# pic3.net
KiCad netlist of a schematic drawn in EAGLE
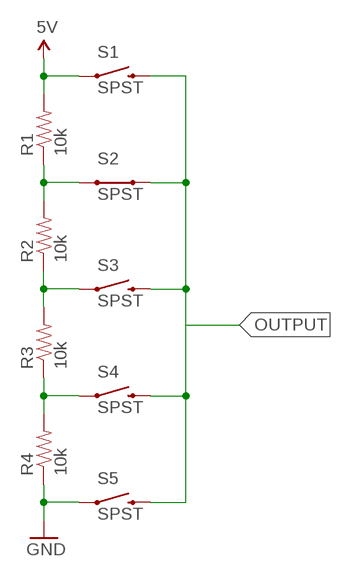
[diagram p0: schematic, sheet 1]

(export (version "E")
  (design (tool "Eeschema 10.0.6"))
  (components
    (comp (ref "R1")
      (value "10k")
      (footprint "eagle-import:0603-RES")
      (fields (field (name "PROD_ID") "RES-00818"))
      (libsource (lib "eagle-import") (part "330OHM1/10W1%(0603)"))
    )
    (comp (ref "R2")
      (value "10k")
      (footprint "eagle-import:0603-RES")
      (fields (field (name "PROD_ID") "RES-00818"))
      (libsource (lib "eagle-import") (part "330OHM1/10W1%(0603)"))
    )
    (comp (ref "R3")
      (value "10k")
      (footprint "eagle-import:0603-RES")
      (fields (field (name "PROD_ID") "RES-00818"))
      (libsource (lib "eagle-import") (part "330OHM1/10W1%(0603)"))
    )
    (comp (ref "R4")
      (value "10k")
      (footprint "eagle-import:0603-RES")
      (fields (field (name "PROD_ID") "RES-00818"))
      (libsource (lib "eagle-import") (part "330OHM1/10W1%(0603)"))
    )
    (comp (ref "S1")
      (value "SPST")
      (footprint "eagle-import:TACTILE-PTH-12MM")
      (libsource (lib "eagle-import") (part "SWITCH-MOMENTARY-212MM"))
    )
    (comp (ref "S2")
      (value "SPST")
      (footprint "eagle-import:TACTILE-PTH-12MM")
      (libsource (lib "eagle-import") (part "SWITCH-MOMENTARY-2-CLOSED"))
    )
    (comp (ref "S3")
      (value "SPST")
      (footprint "eagle-import:TACTILE-PTH-12MM")
      (libsource (lib "eagle-import") (part "SWITCH-MOMENTARY-212MM"))
    )
    (comp (ref "S4")
      (value "SPST")
      (footprint "eagle-import:TACTILE-PTH-12MM")
      (libsource (lib "eagle-import") (part "SWITCH-MOMENTARY-212MM"))
    )
    (comp (ref "S5")
      (value "SPST")
      (footprint "eagle-import:TACTILE-PTH-12MM")
      (libsource (lib "eagle-import") (part "SWITCH-MOMENTARY-212MM"))
    )
  )
  (nets
    (net (code "1") (name "5V") (class "Default")
      (node (ref "R1") (pin "2") (pinfunction "2_2") (pintype "passive"))
      (node (ref "S1") (pin "1") (pinfunction "1_1") (pintype "passive"))
    )
    (net (code "2") (name "GND") (class "Default")
      (node (ref "R4") (pin "1") (pinfunction "1_1") (pintype "passive"))
      (node (ref "S5") (pin "1") (pinfunction "1_1") (pintype "passive"))
    )
    (net (code "3") (name "Net-(R1-Pad1)") (class "Default")
      (node (ref "R1") (pin "1") (pinfunction "1_1") (pintype "passive"))
      (node (ref "R2") (pin "2") (pinfunction "2_2") (pintype "passive"))
      (node (ref "S2") (pin "1") (pinfunction "1_1") (pintype "passive"))
    )
    (net (code "4") (name "Net-(R2-Pad1)") (class "Default")
      (node (ref "R2") (pin "1") (pinfunction "1_1") (pintype "passive"))
      (node (ref "R3") (pin "2") (pinfunction "2_2") (pintype "passive"))
      (node (ref "S3") (pin "1") (pinfunction "1_1") (pintype "passive"))
    )
    (net (code "5") (name "Net-(R3-Pad1)") (class "Default")
      (node (ref "R3") (pin "1") (pinfunction "1_1") (pintype "passive"))
      (node (ref "R4") (pin "2") (pinfunction "2_2") (pintype "passive"))
      (node (ref "S4") (pin "1") (pinfunction "1_1") (pintype "passive"))
    )
    (net (code "6") (name "OUTPUT") (class "Default")
      (node (ref "S1") (pin "3") (pinfunction "2_3") (pintype "passive"))
      (node (ref "S2") (pin "3") (pinfunction "2_3") (pintype "passive"))
      (node (ref "S3") (pin "3") (pinfunction "2_3") (pintype "passive"))
      (node (ref "S4") (pin "3") (pinfunction "2_3") (pintype "passive"))
      (node (ref "S5") (pin "3") (pinfunction "2_3") (pintype "passive"))
    )
  )
)
